# Schematic.net
KiCad netlist of a schematic drawn in EAGLE
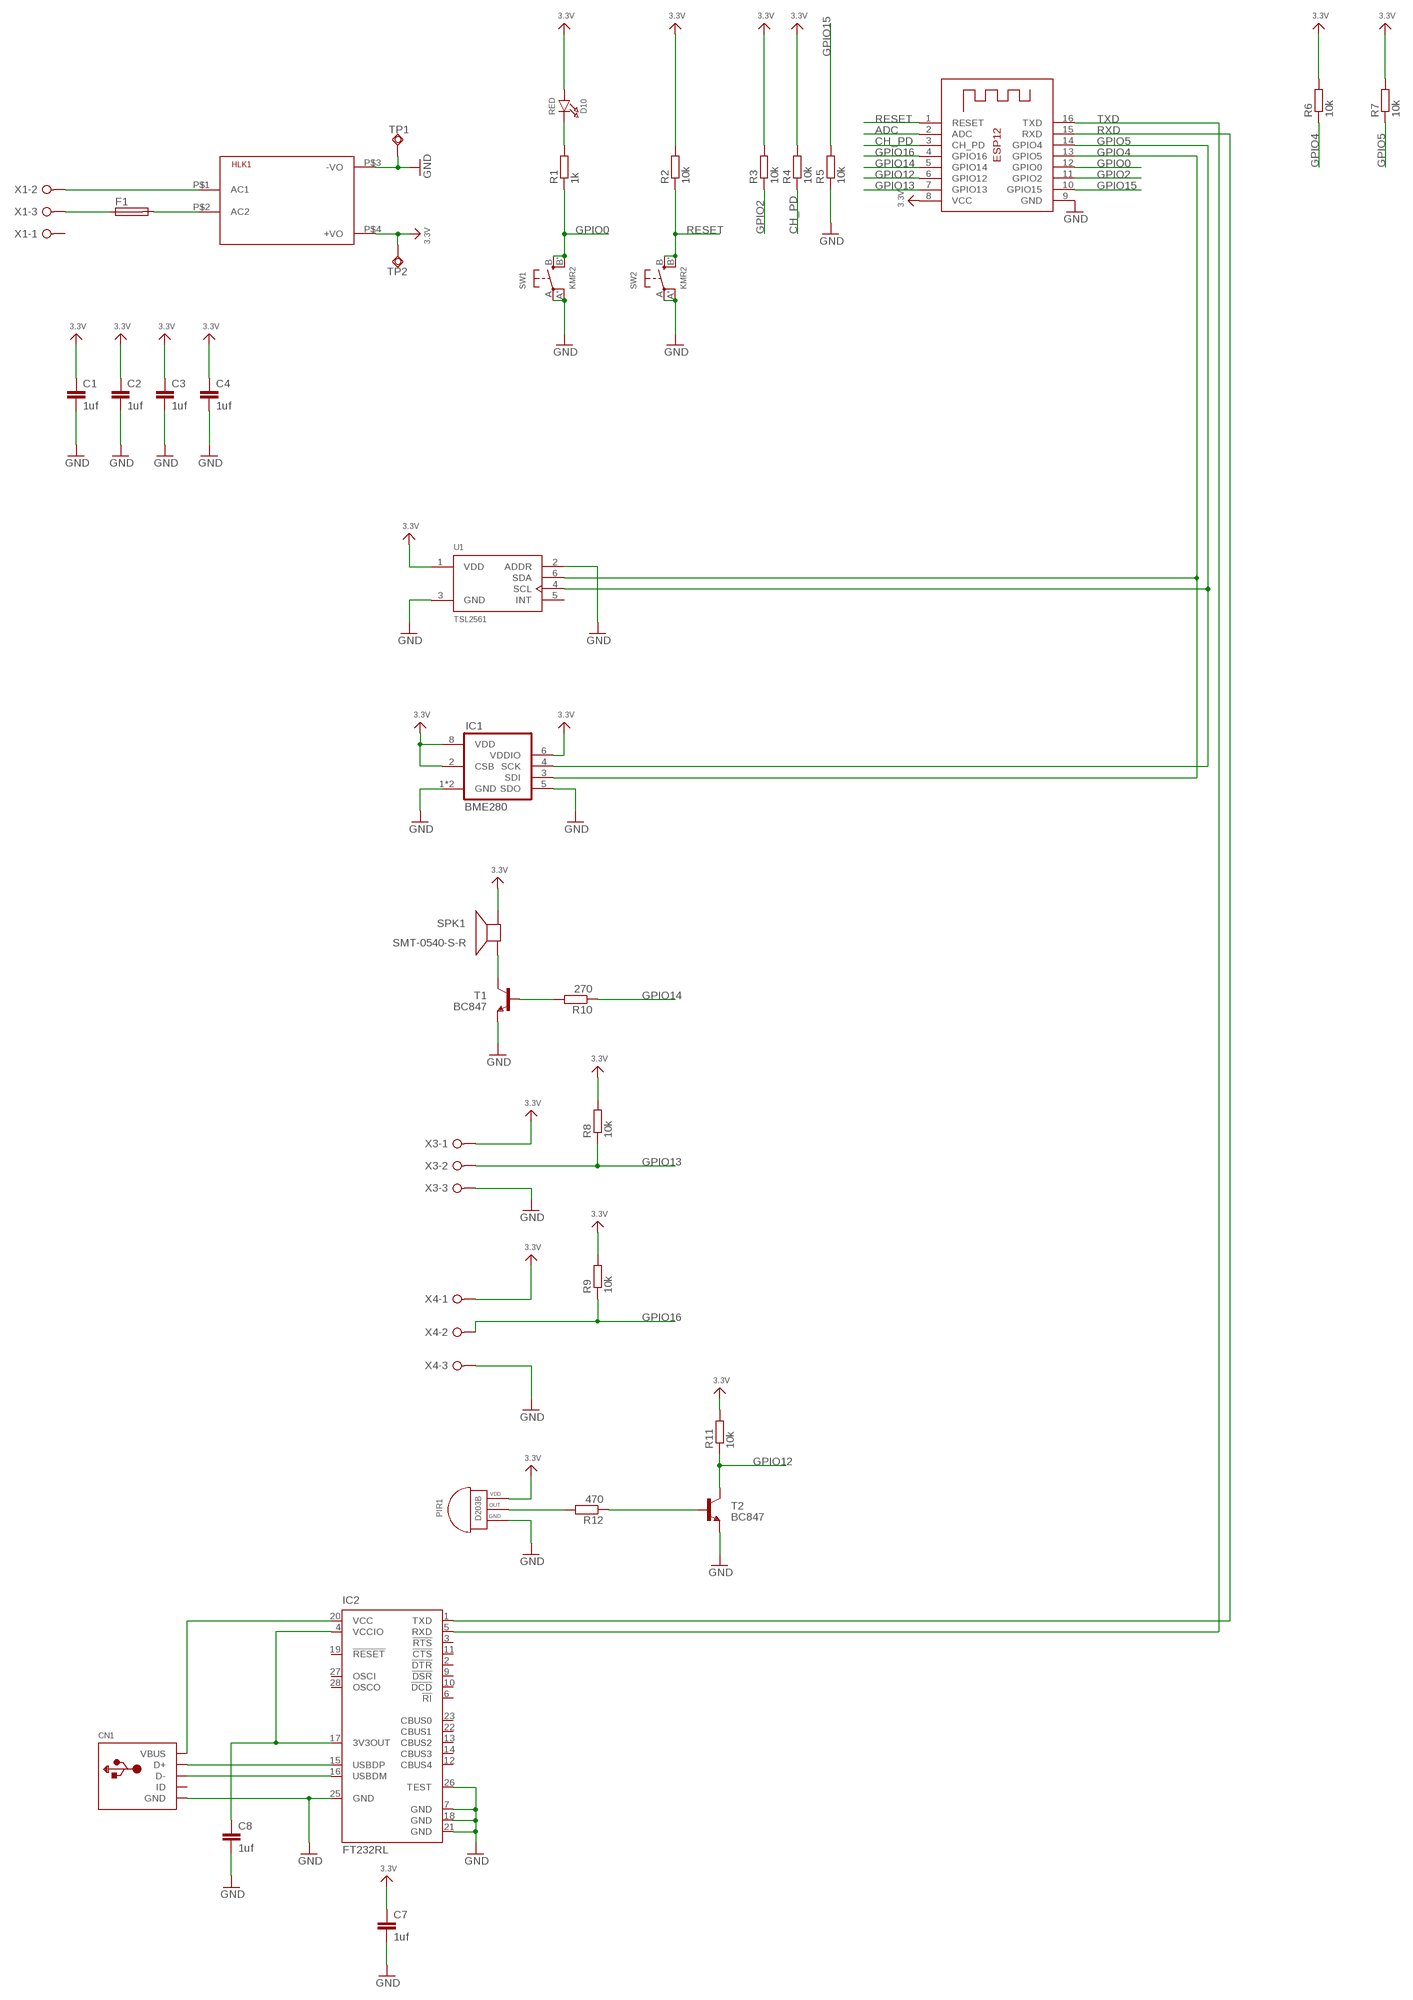
[diagram p0: schematic, sheet 1]

(export (version "E")
  (design (tool "Eeschema 10.0.6"))
  (components
    (comp (ref "C1")
      (value "1uf")
      (footprint "eagle-import:C0805")
      (libsource (lib "eagle-import") (part "C-EUC0805"))
    )
    (comp (ref "C2")
      (value "1uf")
      (footprint "eagle-import:C0805")
      (libsource (lib "eagle-import") (part "C-EUC0805"))
    )
    (comp (ref "C3")
      (value "1uf")
      (footprint "eagle-import:C0805")
      (libsource (lib "eagle-import") (part "C-EUC0805"))
    )
    (comp (ref "C4")
      (value "1uf")
      (footprint "eagle-import:C0805")
      (libsource (lib "eagle-import") (part "C-EUC0805"))
    )
    (comp (ref "C7")
      (value "1uf")
      (footprint "eagle-import:C0805")
      (libsource (lib "eagle-import") (part "C-EUC0805"))
    )
    (comp (ref "C8")
      (value "1uf")
      (footprint "eagle-import:C0805")
      (libsource (lib "eagle-import") (part "C-EUC0805"))
    )
    (comp (ref "CN1")
      (value "USBMINIB")
      (footprint "eagle-import:USB-MINIB")
      (libsource (lib "eagle-import") (part "USBMINIB"))
    )
    (comp (ref "D10")
      (value "RED")
      (footprint "eagle-import:CHIPLED_0805_NOOUTLINE")
      (libsource (lib "eagle-import") (part "LED0805_NOOUTLINE"))
    )
    (comp (ref "F1")
      (value "SH22")
      (footprint "eagle-import:SH22")
      (libsource (lib "eagle-import") (part "SH22"))
    )
    (comp (ref "HLK1")
      (value "HLK-PM013W")
      (footprint "eagle-import:HLK-PM01")
      (libsource (lib "eagle-import") (part "HLK-PM013W"))
    )
    (comp (ref "IC1")
      (value "BME280")
      (footprint "eagle-import:BME280")
      (libsource (lib "eagle-import") (part "BME280"))
    )
    (comp (ref "IC2")
      (value "FT232RL")
      (footprint "eagle-import:SSOP28")
      (libsource (lib "eagle-import") (part "FT232RL"))
    )
    (comp (ref "PIR1")
      (value "D203B")
      (footprint "eagle-import:3PIN")
      (libsource (lib "eagle-import") (part "D203B"))
    )
    (comp (ref "R1")
      (value "1k")
      (footprint "eagle-import:M0805")
      (libsource (lib "eagle-import") (part "R-EU_M0805"))
    )
    (comp (ref "R2")
      (value "10k")
      (footprint "eagle-import:M0805")
      (libsource (lib "eagle-import") (part "R-EU_M0805"))
    )
    (comp (ref "R3")
      (value "10k")
      (footprint "eagle-import:M0805")
      (libsource (lib "eagle-import") (part "R-EU_M0805"))
    )
    (comp (ref "R4")
      (value "10k")
      (footprint "eagle-import:M0805")
      (libsource (lib "eagle-import") (part "R-EU_M0805"))
    )
    (comp (ref "R5")
      (value "10k")
      (footprint "eagle-import:M0805")
      (libsource (lib "eagle-import") (part "R-EU_M0805"))
    )
    (comp (ref "R6")
      (value "10k")
      (footprint "eagle-import:M0805")
      (libsource (lib "eagle-import") (part "R-EU_M0805"))
    )
    (comp (ref "R7")
      (value "10k")
      (footprint "eagle-import:M0805")
      (libsource (lib "eagle-import") (part "R-EU_M0805"))
    )
    (comp (ref "R8")
      (value "10k")
      (footprint "eagle-import:M0805")
      (libsource (lib "eagle-import") (part "R-EU_M0805"))
    )
    (comp (ref "R9")
      (value "10k")
      (footprint "eagle-import:M0805")
      (libsource (lib "eagle-import") (part "R-EU_M0805"))
    )
    (comp (ref "R10")
      (value "270")
      (footprint "eagle-import:M0805")
      (libsource (lib "eagle-import") (part "R-EU_M0805"))
    )
    (comp (ref "R11")
      (value "10k")
      (footprint "eagle-import:M0805")
      (libsource (lib "eagle-import") (part "R-EU_M0805"))
    )
    (comp (ref "R12")
      (value "470")
      (footprint "eagle-import:M0805")
      (libsource (lib "eagle-import") (part "R-EU_M0805"))
    )
    (comp (ref "SPK1")
      (value "SMT-0540-S-R")
      (footprint "eagle-import:SMT-0540-S-R")
      (libsource (lib "eagle-import") (part "SMT-0540-S-R"))
    )
    (comp (ref "SW1")
      (value "KMR2")
      (footprint "eagle-import:BTN_KMR2_4.6X2.8")
      (libsource (lib "eagle-import") (part "SWITCH_TACT_SMT4.6X2.8"))
    )
    (comp (ref "SW2")
      (value "KMR2")
      (footprint "eagle-import:BTN_KMR2_4.6X2.8")
      (libsource (lib "eagle-import") (part "SWITCH_TACT_SMT4.6X2.8"))
    )
    (comp (ref "T1")
      (value "BC847")
      (footprint "eagle-import:SOT23")
      (libsource (lib "eagle-import") (part "BC847"))
    )
    (comp (ref "T2")
      (value "BC847")
      (footprint "eagle-import:SOT23")
      (libsource (lib "eagle-import") (part "BC847"))
    )
    (comp (ref "TP1")
      (value "TPSQPAD1-13Y")
      (footprint "eagle-import:P1-13Y")
      (libsource (lib "eagle-import") (part "TPSQPAD1-13Y"))
    )
    (comp (ref "TP2")
      (value "TPSQPAD1-13Y")
      (footprint "eagle-import:P1-13Y")
      (libsource (lib "eagle-import") (part "TPSQPAD1-13Y"))
    )
    (comp (ref "U1")
      (value "TSL2561")
      (footprint "eagle-import:TMB-6")
      (libsource (lib "eagle-import") (part "TSL2561"))
    )
    (comp (ref "X1")
      (value "W237-03P")
      (footprint "eagle-import:W237-133")
      (libsource (lib "eagle-import") (part "W237-03P"))
    )
    (comp (ref "X2")
      (value "ESP-12")
      (footprint "eagle-import:ESP-12")
      (libsource (lib "eagle-import") (part "ESP-12"))
    )
    (comp (ref "X3")
      (value "W237-03P")
      (footprint "eagle-import:W237-133")
      (libsource (lib "eagle-import") (part "W237-03P"))
    )
    (comp (ref "X4")
      (value "W237-03P")
      (footprint "eagle-import:W237-133")
      (libsource (lib "eagle-import") (part "W237-03P"))
    )
  )
  (nets
    (net (code "1") (name "/ADC") (class "Default")
      (node (ref "X2") (pin "2") (pinfunction "ADC_2") (pintype "passive"))
    )
    (net (code "2") (name "/CH_PD") (class "Default")
      (node (ref "R4") (pin "1") (pinfunction "1_1") (pintype "passive"))
      (node (ref "X2") (pin "3") (pinfunction "CH_PD_3") (pintype "input"))
    )
    (net (code "3") (name "/GPIO0") (class "Default")
      (node (ref "R1") (pin "1") (pinfunction "1_1") (pintype "passive"))
      (node (ref "SW1") (pin "B") (pinfunction "S_B") (pintype "passive"))
      (node (ref "SW1") (pin "B'") (pinfunction "S1_B'") (pintype "passive"))
      (node (ref "X2") (pin "12") (pinfunction "GPIO0_12") (pintype "bidirectional"))
    )
    (net (code "4") (name "/GPIO2") (class "Default")
      (node (ref "R3") (pin "1") (pinfunction "1_1") (pintype "passive"))
      (node (ref "X2") (pin "11") (pinfunction "GPIO2_11") (pintype "bidirectional"))
    )
    (net (code "5") (name "/GPIO4") (class "Default")
      (node (ref "IC1") (pin "3") (pinfunction "SDI_3") (pintype "bidirectional"))
      (node (ref "R6") (pin "1") (pinfunction "1_1") (pintype "passive"))
      (node (ref "U1") (pin "6") (pinfunction "SDA_6") (pintype "bidirectional"))
      (node (ref "X2") (pin "13") (pinfunction "GPIO5_13") (pintype "bidirectional"))
    )
    (net (code "6") (name "/GPIO5") (class "Default")
      (node (ref "IC1") (pin "4") (pinfunction "SCK_4") (pintype "bidirectional"))
      (node (ref "R7") (pin "1") (pinfunction "1_1") (pintype "passive"))
      (node (ref "U1") (pin "4") (pinfunction "SCL_4") (pintype "input"))
      (node (ref "X2") (pin "14") (pinfunction "GPIO4_14") (pintype "bidirectional"))
    )
    (net (code "7") (name "/GPIO12") (class "Default")
      (node (ref "R11") (pin "1") (pinfunction "1_1") (pintype "passive"))
      (node (ref "T2") (pin "3") (pinfunction "C_3") (pintype "passive"))
      (node (ref "X2") (pin "6") (pinfunction "GPIO12_6") (pintype "bidirectional"))
    )
    (net (code "8") (name "/GPIO13") (class "Default")
      (node (ref "R8") (pin "1") (pinfunction "1_1") (pintype "passive"))
      (node (ref "X2") (pin "7") (pinfunction "GPIO13_7") (pintype "bidirectional"))
      (node (ref "X3") (pin "2") (pinfunction "KL_2") (pintype "passive"))
    )
    (net (code "9") (name "/GPIO14") (class "Default")
      (node (ref "R10") (pin "1") (pinfunction "1_1") (pintype "passive"))
      (node (ref "X2") (pin "5") (pinfunction "GPIO14_5") (pintype "bidirectional"))
    )
    (net (code "10") (name "/GPIO15") (class "Default")
      (node (ref "R5") (pin "2") (pinfunction "2_2") (pintype "passive"))
      (node (ref "X2") (pin "10") (pinfunction "GPIO15_10") (pintype "bidirectional"))
    )
    (net (code "11") (name "/GPIO16") (class "Default")
      (node (ref "R9") (pin "1") (pinfunction "1_1") (pintype "passive"))
      (node (ref "X2") (pin "4") (pinfunction "GPIO16_4") (pintype "bidirectional"))
      (node (ref "X4") (pin "2") (pinfunction "KL_2") (pintype "passive"))
    )
    (net (code "12") (name "/RESET") (class "Default")
      (node (ref "R2") (pin "1") (pinfunction "1_1") (pintype "passive"))
      (node (ref "SW2") (pin "B") (pinfunction "S_B") (pintype "passive"))
      (node (ref "SW2") (pin "B'") (pinfunction "S1_B'") (pintype "passive"))
      (node (ref "X2") (pin "1") (pinfunction "RESET_1") (pintype "input"))
    )
    (net (code "13") (name "/RXD") (class "Default")
      (node (ref "IC2") (pin "1") (pinfunction "TXD_1") (pintype "output"))
      (node (ref "X2") (pin "15") (pinfunction "RXD_15") (pintype "input"))
    )
    (net (code "14") (name "/TXD") (class "Default")
      (node (ref "IC2") (pin "5") (pinfunction "RXD_5") (pintype "input"))
      (node (ref "X2") (pin "16") (pinfunction "TXD_16") (pintype "output"))
    )
    (net (code "15") (name "3.3V") (class "Default")
      (node (ref "C1") (pin "1") (pinfunction "1_1") (pintype "passive"))
      (node (ref "C2") (pin "1") (pinfunction "1_1") (pintype "passive"))
      (node (ref "C3") (pin "1") (pinfunction "1_1") (pintype "passive"))
      (node (ref "C4") (pin "1") (pinfunction "1_1") (pintype "passive"))
      (node (ref "C7") (pin "1") (pinfunction "1_1") (pintype "passive"))
      (node (ref "D10") (pin "A") (pinfunction "A_A") (pintype "passive"))
      (node (ref "HLK1") (pin "P$4") (pinfunction "+VO_P$4") (pintype "bidirectional"))
      (node (ref "IC1") (pin "2") (pinfunction "CSB_2") (pintype "input"))
      (node (ref "IC1") (pin "6") (pinfunction "VDDIO_6") (pintype "power_in"))
      (node (ref "IC1") (pin "8") (pinfunction "VDD_8") (pintype "power_in"))
      (node (ref "PIR1") (pin "1") (pinfunction "VDD_1") (pintype "bidirectional"))
      (node (ref "R11") (pin "2") (pinfunction "2_2") (pintype "passive"))
      (node (ref "R2") (pin "2") (pinfunction "2_2") (pintype "passive"))
      (node (ref "R3") (pin "2") (pinfunction "2_2") (pintype "passive"))
      (node (ref "R4") (pin "2") (pinfunction "2_2") (pintype "passive"))
      (node (ref "R6") (pin "2") (pinfunction "2_2") (pintype "passive"))
      (node (ref "R7") (pin "2") (pinfunction "2_2") (pintype "passive"))
      (node (ref "R8") (pin "2") (pinfunction "2_2") (pintype "passive"))
      (node (ref "R9") (pin "2") (pinfunction "2_2") (pintype "passive"))
      (node (ref "SPK1") (pin "+") (pinfunction "-_+") (pintype "passive"))
      (node (ref "TP2") (pin "TP") (pinfunction "TP_TP") (pintype "input"))
      (node (ref "U1") (pin "1") (pinfunction "VDD_1") (pintype "power_in"))
      (node (ref "X2") (pin "8") (pinfunction "VCC_8") (pintype "power_in"))
      (node (ref "X3") (pin "1") (pinfunction "KL_1") (pintype "passive"))
      (node (ref "X4") (pin "1") (pinfunction "KL_1") (pintype "passive"))
    )
    (net (code "16") (name "GND") (class "Default")
      (node (ref "C1") (pin "2") (pinfunction "2_2") (pintype "passive"))
      (node (ref "C2") (pin "2") (pinfunction "2_2") (pintype "passive"))
      (node (ref "C3") (pin "2") (pinfunction "2_2") (pintype "passive"))
      (node (ref "C4") (pin "2") (pinfunction "2_2") (pintype "passive"))
      (node (ref "C7") (pin "2") (pinfunction "2_2") (pintype "passive"))
      (node (ref "C8") (pin "2") (pinfunction "2_2") (pintype "passive"))
      (node (ref "CN1") (pin "GND") (pinfunction "GND_GND") (pintype "power_in"))
      (node (ref "HLK1") (pin "P$3") (pinfunction "-VO_P$3") (pintype "bidirectional"))
      (node (ref "IC1") (pin "1") (pinfunction "GND_1") (pintype "power_in"))
      (node (ref "IC1") (pin "5") (pinfunction "SDO_5") (pintype "input"))
      (node (ref "IC1") (pin "7") (pinfunction "GND_7") (pintype "power_in"))
      (node (ref "IC2") (pin "18") (pinfunction "GND_18") (pintype "power_in"))
      (node (ref "IC2") (pin "21") (pinfunction "GND_21") (pintype "power_in"))
      (node (ref "IC2") (pin "25") (pinfunction "GND_25") (pintype "power_in"))
      (node (ref "IC2") (pin "26") (pinfunction "TEST_26") (pintype "input"))
      (node (ref "IC2") (pin "7") (pinfunction "GND_7") (pintype "power_in"))
      (node (ref "PIR1") (pin "3") (pinfunction "GND_3") (pintype "bidirectional"))
      (node (ref "R5") (pin "1") (pinfunction "1_1") (pintype "passive"))
      (node (ref "SW1") (pin "A") (pinfunction "P_A") (pintype "passive"))
      (node (ref "SW1") (pin "A'") (pinfunction "P1_A'") (pintype "passive"))
      (node (ref "SW2") (pin "A") (pinfunction "P_A") (pintype "passive"))
      (node (ref "SW2") (pin "A'") (pinfunction "P1_A'") (pintype "passive"))
      (node (ref "T1") (pin "2") (pinfunction "E_2") (pintype "passive"))
      (node (ref "T2") (pin "2") (pinfunction "E_2") (pintype "passive"))
      (node (ref "TP1") (pin "TP") (pinfunction "TP_TP") (pintype "input"))
      (node (ref "U1") (pin "2") (pinfunction "ADDR_2") (pintype "input"))
      (node (ref "U1") (pin "3") (pinfunction "GND_3") (pintype "power_in"))
      (node (ref "X2") (pin "9") (pinfunction "GND_9") (pintype "power_in"))
      (node (ref "X3") (pin "3") (pinfunction "KL_3") (pintype "passive"))
      (node (ref "X4") (pin "3") (pinfunction "KL_3") (pintype "passive"))
    )
    (net (code "17") (name "Net-(D10-PadC)") (class "Default")
      (node (ref "D10") (pin "C") (pinfunction "C_C") (pintype "passive"))
      (node (ref "R1") (pin "2") (pinfunction "2_2") (pintype "passive"))
    )
    (net (code "18") (name "Net-(HLK1-AC1)") (class "Default")
      (node (ref "HLK1") (pin "P$1") (pinfunction "AC1_P$1") (pintype "bidirectional"))
      (node (ref "X1") (pin "2") (pinfunction "KL_2") (pintype "passive"))
    )
    (net (code "19") (name "Net-(HLK1-AC2)") (class "Default")
      (node (ref "F1") (pin "2") (pinfunction "2_2") (pintype "passive"))
      (node (ref "HLK1") (pin "P$2") (pinfunction "AC2_P$2") (pintype "bidirectional"))
    )
    (net (code "20") (name "Net-(IC2-3V3OUT)") (class "Default")
      (node (ref "C8") (pin "1") (pinfunction "1_1") (pintype "passive"))
      (node (ref "IC2") (pin "17") (pinfunction "3V3OUT_17") (pintype "output"))
      (node (ref "IC2") (pin "4") (pinfunction "VCCIO_4") (pintype "power_in"))
    )
    (net (code "21") (name "Net-(IC2-USBDM)") (class "Default")
      (node (ref "CN1") (pin "D-") (pinfunction "D-_D-") (pintype "bidirectional"))
      (node (ref "IC2") (pin "16") (pinfunction "USBDM_16") (pintype "bidirectional"))
    )
    (net (code "22") (name "Net-(IC2-USBDP)") (class "Default")
      (node (ref "CN1") (pin "D+") (pinfunction "D+_D+") (pintype "bidirectional"))
      (node (ref "IC2") (pin "15") (pinfunction "USBDP_15") (pintype "bidirectional"))
    )
    (net (code "23") (name "Net-(IC2-VCC)") (class "Default")
      (node (ref "CN1") (pin "VBUS") (pinfunction "VBUS_VBUS") (pintype "power_in"))
      (node (ref "IC2") (pin "20") (pinfunction "VCC_20") (pintype "power_in"))
    )
    (net (code "24") (name "Net-(PIR1-OUT)") (class "Default")
      (node (ref "PIR1") (pin "2") (pinfunction "OUT_2") (pintype "bidirectional"))
      (node (ref "R12") (pin "2") (pinfunction "2_2") (pintype "passive"))
    )
    (net (code "25") (name "Net-(SPK1-+)") (class "Default")
      (node (ref "SPK1") (pin "-") (pinfunction "+_-") (pintype "passive"))
      (node (ref "T1") (pin "3") (pinfunction "C_3") (pintype "passive"))
    )
    (net (code "26") (name "Net-(T1-B)") (class "Default")
      (node (ref "R10") (pin "2") (pinfunction "2_2") (pintype "passive"))
      (node (ref "T1") (pin "1") (pinfunction "B_1") (pintype "passive"))
    )
    (net (code "27") (name "Net-(T2-B)") (class "Default")
      (node (ref "R12") (pin "1") (pinfunction "1_1") (pintype "passive"))
      (node (ref "T2") (pin "1") (pinfunction "B_1") (pintype "passive"))
    )
    (net (code "28") (name "Net-(X1C-KL)") (class "Default")
      (node (ref "F1") (pin "1") (pinfunction "1_1") (pintype "passive"))
      (node (ref "X1") (pin "3") (pinfunction "KL_3") (pintype "passive"))
    )
    (net (code "29") (name "unconnected-(CN1-PadID)") (class "Default")
      (node (ref "CN1") (pin "ID") (pinfunction "ID_ID") (pintype "bidirectional"))
    )
    (net (code "30") (name "unconnected-(IC2-CBUS0-Pad23)") (class "Default")
      (node (ref "IC2") (pin "23") (pinfunction "CBUS0_23") (pintype "bidirectional"))
    )
    (net (code "31") (name "unconnected-(IC2-CBUS1-Pad22)") (class "Default")
      (node (ref "IC2") (pin "22") (pinfunction "CBUS1_22") (pintype "bidirectional"))
    )
    (net (code "32") (name "unconnected-(IC2-CBUS2-Pad13)") (class "Default")
      (node (ref "IC2") (pin "13") (pinfunction "CBUS2_13") (pintype "bidirectional"))
    )
    (net (code "33") (name "unconnected-(IC2-CBUS3-Pad14)") (class "Default")
      (node (ref "IC2") (pin "14") (pinfunction "CBUS3_14") (pintype "bidirectional"))
    )
    (net (code "34") (name "unconnected-(IC2-CBUS4-Pad12)") (class "Default")
      (node (ref "IC2") (pin "12") (pinfunction "CBUS4_12") (pintype "bidirectional"))
    )
    (net (code "35") (name "unconnected-(IC2-OSCI-Pad27)") (class "Default")
      (node (ref "IC2") (pin "27") (pinfunction "OSCI_27") (pintype "input"))
    )
    (net (code "36") (name "unconnected-(IC2-OSCO-Pad28)") (class "Default")
      (node (ref "IC2") (pin "28") (pinfunction "OSCO_28") (pintype "output"))
    )
    (net (code "37") (name "unconnected-(IC2-~{CTS}-Pad11)") (class "Default")
      (node (ref "IC2") (pin "11") (pinfunction "~{CTS}_11") (pintype "input"))
    )
    (net (code "38") (name "unconnected-(IC2-~{DCD}-Pad10)") (class "Default")
      (node (ref "IC2") (pin "10") (pinfunction "~{DCD}_10") (pintype "input"))
    )
    (net (code "39") (name "unconnected-(IC2-~{DSR}-Pad9)") (class "Default")
      (node (ref "IC2") (pin "9") (pinfunction "~{DSR}_9") (pintype "input"))
    )
    (net (code "40") (name "unconnected-(IC2-~{DTR}-Pad2)") (class "Default")
      (node (ref "IC2") (pin "2") (pinfunction "~{DTR}_2") (pintype "output"))
    )
    (net (code "41") (name "unconnected-(IC2-~{RESET}-Pad19)") (class "Default")
      (node (ref "IC2") (pin "19") (pinfunction "~{RESET}_19") (pintype "input"))
    )
    (net (code "42") (name "unconnected-(IC2-~{RI}-Pad6)") (class "Default")
      (node (ref "IC2") (pin "6") (pinfunction "~{RI}_6") (pintype "input"))
    )
    (net (code "43") (name "unconnected-(IC2-~{RTS}-Pad3)") (class "Default")
      (node (ref "IC2") (pin "3") (pinfunction "~{RTS}_3") (pintype "output"))
    )
    (net (code "44") (name "unconnected-(U1-INT-Pad5)") (class "Default")
      (node (ref "U1") (pin "5") (pinfunction "INT_5") (pintype "output"))
    )
    (net (code "45") (name "unconnected-(X1A-KL-Pad1)") (class "Default")
      (node (ref "X1") (pin "1") (pinfunction "KL_1") (pintype "passive"))
    )
  )
)
